# breakout-v2.net
KiCad netlist of a schematic drawn in EAGLE
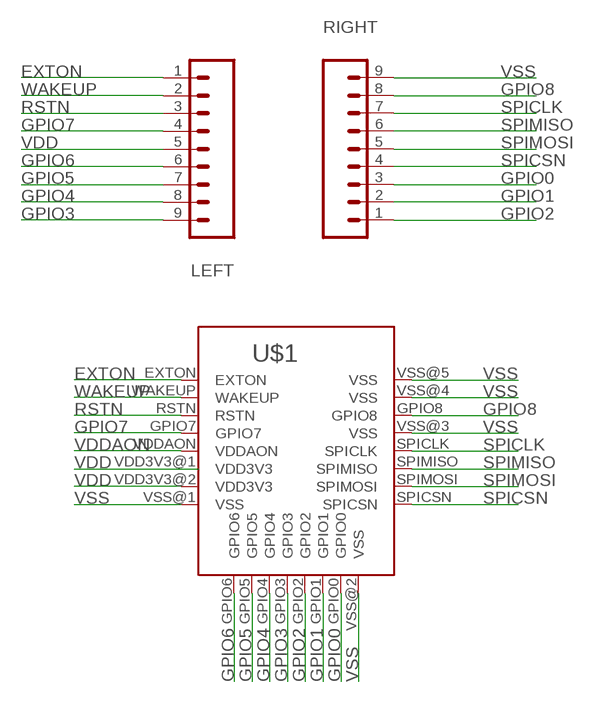
[diagram p0: schematic, sheet 1]

(export (version "E")
  (design (tool "Eeschema 10.0.6"))
  (components
    (comp (ref "LEFT")
      (value "M09")
      (footprint "eagle-import:1X09")
      (libsource (lib "eagle-import") (part "M09"))
    )
    (comp (ref "RIGHT")
      (value "M09")
      (footprint "eagle-import:1X09")
      (libsource (lib "eagle-import") (part "M09"))
    )
    (comp (ref "U$1")
      (value "DWM1000")
      (footprint "eagle-import:DWM1000")
      (libsource (lib "eagle-import") (part "DWM1000"))
    )
  )
  (nets
    (net (code "1") (name "/EXTON") (class "Default")
      (node (ref "LEFT") (pin "1") (pinfunction "1_1") (pintype "passive"))
      (node (ref "U$1") (pin "EXTON") (pinfunction "EXTON_EXTON") (pintype "bidirectional"))
    )
    (net (code "2") (name "/GPIO0") (class "Default")
      (node (ref "RIGHT") (pin "3") (pinfunction "3_3") (pintype "passive"))
      (node (ref "U$1") (pin "GPIO0") (pinfunction "GPIO0_GPIO0") (pintype "bidirectional"))
    )
    (net (code "3") (name "/GPIO1") (class "Default")
      (node (ref "RIGHT") (pin "2") (pinfunction "2_2") (pintype "passive"))
      (node (ref "U$1") (pin "GPIO1") (pinfunction "GPIO1_GPIO1") (pintype "bidirectional"))
    )
    (net (code "4") (name "/GPIO2") (class "Default")
      (node (ref "RIGHT") (pin "1") (pinfunction "1_1") (pintype "passive"))
      (node (ref "U$1") (pin "GPIO2") (pinfunction "GPIO2_GPIO2") (pintype "bidirectional"))
    )
    (net (code "5") (name "/GPIO3") (class "Default")
      (node (ref "LEFT") (pin "9") (pinfunction "9_9") (pintype "passive"))
      (node (ref "U$1") (pin "GPIO3") (pinfunction "GPIO3_GPIO3") (pintype "bidirectional"))
    )
    (net (code "6") (name "/GPIO4") (class "Default")
      (node (ref "LEFT") (pin "8") (pinfunction "8_8") (pintype "passive"))
      (node (ref "U$1") (pin "GPIO4") (pinfunction "GPIO4_GPIO4") (pintype "bidirectional"))
    )
    (net (code "7") (name "/GPIO5") (class "Default")
      (node (ref "LEFT") (pin "7") (pinfunction "7_7") (pintype "passive"))
      (node (ref "U$1") (pin "GPIO5") (pinfunction "GPIO5_GPIO5") (pintype "bidirectional"))
    )
    (net (code "8") (name "/GPIO6") (class "Default")
      (node (ref "LEFT") (pin "6") (pinfunction "6_6") (pintype "passive"))
      (node (ref "U$1") (pin "GPIO6") (pinfunction "GPIO6_GPIO6") (pintype "bidirectional"))
    )
    (net (code "9") (name "/GPIO7") (class "Default")
      (node (ref "LEFT") (pin "4") (pinfunction "4_4") (pintype "passive"))
      (node (ref "U$1") (pin "GPIO7") (pinfunction "GPIO7_GPIO7") (pintype "bidirectional"))
    )
    (net (code "10") (name "/GPIO8") (class "Default")
      (node (ref "RIGHT") (pin "8") (pinfunction "8_8") (pintype "passive"))
      (node (ref "U$1") (pin "GPIO8") (pinfunction "GPIO8_GPIO8") (pintype "bidirectional"))
    )
    (net (code "11") (name "/RSTN") (class "Default")
      (node (ref "LEFT") (pin "3") (pinfunction "3_3") (pintype "passive"))
      (node (ref "U$1") (pin "RSTN") (pinfunction "RSTN_RSTN") (pintype "bidirectional"))
    )
    (net (code "12") (name "/SPICLK") (class "Default")
      (node (ref "RIGHT") (pin "7") (pinfunction "7_7") (pintype "passive"))
      (node (ref "U$1") (pin "SPICLK") (pinfunction "SPICLK_SPICLK") (pintype "bidirectional"))
    )
    (net (code "13") (name "/SPICSN") (class "Default")
      (node (ref "RIGHT") (pin "4") (pinfunction "4_4") (pintype "passive"))
      (node (ref "U$1") (pin "SPICSN") (pinfunction "SPICSN_SPICSN") (pintype "bidirectional"))
    )
    (net (code "14") (name "/SPIMISO") (class "Default")
      (node (ref "RIGHT") (pin "6") (pinfunction "6_6") (pintype "passive"))
      (node (ref "U$1") (pin "SPIMISO") (pinfunction "SPIMISO_SPIMISO") (pintype "bidirectional"))
    )
    (net (code "15") (name "/SPIMOSI") (class "Default")
      (node (ref "RIGHT") (pin "5") (pinfunction "5_5") (pintype "passive"))
      (node (ref "U$1") (pin "SPIMOSI") (pinfunction "SPIMOSI_SPIMOSI") (pintype "bidirectional"))
    )
    (net (code "16") (name "/VDD") (class "Default")
      (node (ref "LEFT") (pin "5") (pinfunction "5_5") (pintype "passive"))
      (node (ref "U$1") (pin "VDD3V3@2") (pinfunction "VDD3V3_VDD3V3@2") (pintype "power_in"))
    )
    (net (code "17") (name "/VDD3V3") (class "Default")
      (node (ref "U$1") (pin "VDD3V3@1") (pinfunction "VDD3V3_VDD3V3@1") (pintype "power_in"))
    )
    (net (code "18") (name "/VDDAON") (class "Default")
      (node (ref "U$1") (pin "VDDAON") (pinfunction "VDDAON_VDDAON") (pintype "power_in"))
    )
    (net (code "19") (name "/VSS") (class "Default")
      (node (ref "RIGHT") (pin "9") (pinfunction "9_9") (pintype "passive"))
      (node (ref "U$1") (pin "VSS@1") (pinfunction "VSS_VSS@1") (pintype "power_in"))
      (node (ref "U$1") (pin "VSS@2") (pinfunction "VSS_VSS@2") (pintype "power_in"))
      (node (ref "U$1") (pin "VSS@3") (pinfunction "VSS_VSS@3") (pintype "power_in"))
      (node (ref "U$1") (pin "VSS@4") (pinfunction "VSS_VSS@4") (pintype "power_in"))
      (node (ref "U$1") (pin "VSS@5") (pinfunction "VSS_VSS@5") (pintype "power_in"))
    )
    (net (code "20") (name "/WAKEUP") (class "Default")
      (node (ref "LEFT") (pin "2") (pinfunction "2_2") (pintype "passive"))
      (node (ref "U$1") (pin "WAKEUP") (pinfunction "WAKEUP_WAKEUP") (pintype "bidirectional"))
    )
  )
)
